# mcu.net
KiCad netlist of a schematic drawn in Altium Designer
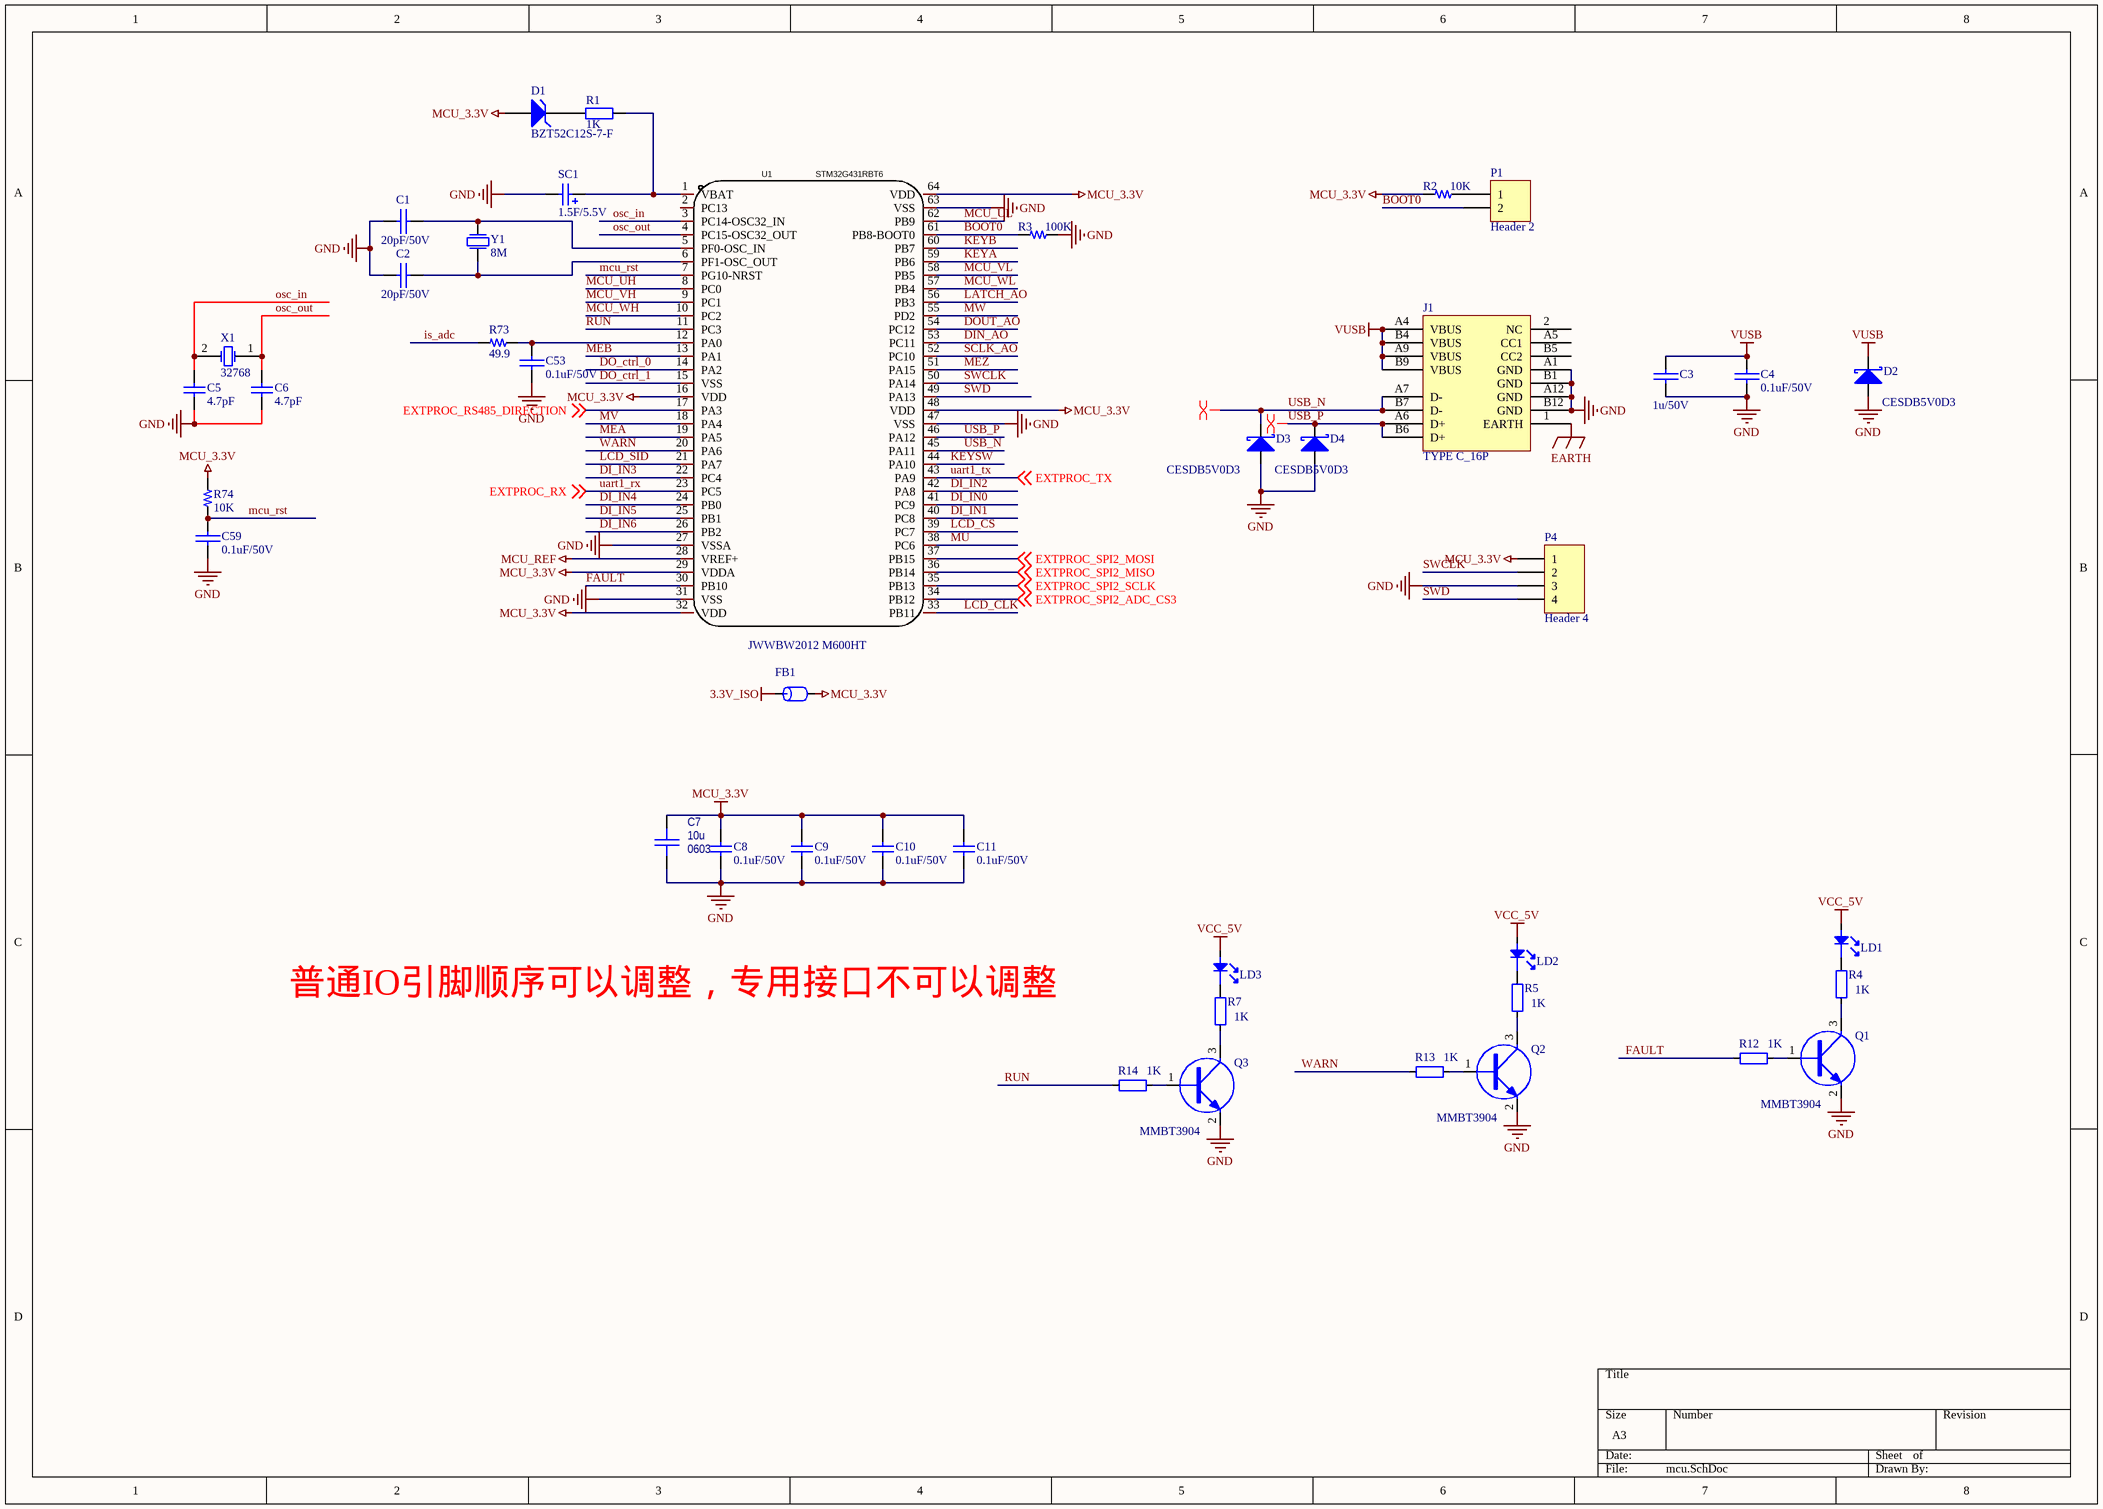
[diagram p0: mcu.SchDoc]

(export (version "E")
  (design (tool "Eeschema 10.0.6"))
  (components
    (comp (ref "C1")
      (value "20pF/50V")
      (footprint "0603C")
      (fields (field (name "Comment") "20pF/25V"))
      (libsource (lib "SM") (part "CAP"))
    )
    (comp (ref "C2")
      (value "20pF/50V")
      (footprint "0603C")
      (fields (field (name "Comment") "20pF/25V"))
      (libsource (lib "SM") (part "CAP"))
    )
    (comp (ref "C3")
      (value "1u/50V")
      (footprint "0603C")
      (fields (field (name "Comment") "1uF/25V"))
      (libsource (lib "SM") (part "CAP"))
    )
    (comp (ref "C4") (value "0.1uF/50V") (footprint "0603C") (libsource (lib "SM") (part "CAP")))
    (comp (ref "C5")
      (value "4.7pF")
      (footprint "0603C")
      (description "Capacitor")
      (fields (field (name "PUBLISHER") "Altium Limited"))
      (libsource (lib "Miscellaneous Devices") (part "Cap"))
    )
    (comp (ref "C6")
      (value "4.7pF")
      (footprint "0603C")
      (description "Capacitor")
      (fields (field (name "PUBLISHER") "Altium Limited"))
      (libsource (lib "Miscellaneous Devices") (part "Cap"))
    )
    (comp (ref "C7")
      (value "10u")
      (footprint "CAPC1608X092N_0603")
      (description "Capacitor, MLCC")
      (fields
        (field (name "MANUFACTURER") "Murata Electronics")
        (field (name "PARTNUMBER") "GRM188R61A106KE69D")
        (field (name "PACKAGE") "0603")
      )
      (libsource (lib "Karl") (part "Capacitor_0603"))
    )
    (comp (ref "C8")
      (value "0.1uF/50V")
      (footprint "0603C")
      (description "Capacitor")
      (fields (field (name "PUBLISHER") "Altium Limited"))
      (libsource (lib "Miscellaneous Devices") (part "Cap"))
    )
    (comp (ref "C9")
      (value "0.1uF/50V")
      (footprint "0603C")
      (description "Capacitor")
      (fields (field (name "PUBLISHER") "Altium Limited"))
      (libsource (lib "Miscellaneous Devices") (part "Cap"))
    )
    (comp (ref "C10")
      (value "0.1uF/50V")
      (footprint "0603C")
      (description "Capacitor")
      (fields (field (name "PUBLISHER") "Altium Limited"))
      (libsource (lib "Miscellaneous Devices") (part "Cap"))
    )
    (comp (ref "C11")
      (value "0.1uF/50V")
      (footprint "0603C")
      (description "Capacitor")
      (fields (field (name "PUBLISHER") "Altium Limited"))
      (libsource (lib "Miscellaneous Devices") (part "Cap"))
    )
    (comp (ref "C53") (value "0.1uF/50V") (footprint "0603C") (libsource (lib "SM") (part "CAP")))
    (comp (ref "C59") (value "0.1uF/50V") (footprint "0603C") (libsource (lib "SM") (part "CAP")))
    (comp (ref "D1")
      (value "BZT52C12S-7-F")
      (footprint "DIOD-SOD323-2_V")
      (libsource (lib "Bogen") (part "BZT52C12S-7-F"))
    )
    (comp (ref "D2") (value "CESDB5V0D3") (footprint "SOD323") (libsource (lib "*") (part "DIODE S")))
    (comp (ref "D3") (value "CESDB5V0D3") (footprint "SOD323") (libsource (lib "*") (part "DIODE S")))
    (comp (ref "D4") (value "CESDB5V0D3") (footprint "SOD323") (libsource (lib "*") (part "DIODE S")))
    (comp (ref "FB1")
      (value "JWWBW2012 M600HT")
      (footprint "0805R")
      (libsource (lib "Schlib_20110825") (part "FB"))
    )
    (comp (ref "J1")
      (value "TYPE C_16P")
      (footprint "TYPEC_16P")
      (libsource (lib "Schlib_20110825") (part "TYPE C_16P"))
    )
    (comp (ref "LD1")
      (value "LED_Green_19-217")
      (footprint "0603led")
      (libsource (lib "RC_M_D_00") (part "LED_Green_19-217"))
    )
    (comp (ref "LD2")
      (value "LED_Green_19-217")
      (footprint "0603led")
      (libsource (lib "RC_M_D_00") (part "LED_Green_19-217"))
    )
    (comp (ref "LD3")
      (value "LED_Green_19-217")
      (footprint "0603led")
      (libsource (lib "RC_M_D_00") (part "LED_Green_19-217"))
    )
    (comp (ref "P1")
      (value "Header 2")
      (footprint "HDR1X2")
      (fields (field (name "PUBLISHER") "Altium Limited"))
      (libsource (lib "Miscellaneous Connectors") (part "Header 2"))
    )
    (comp (ref "P4")
      (value "Header 4")
      (footprint "HDR1X4")
      (fields (field (name "PUBLISHER") "Altium Limited"))
      (libsource (lib "Miscellaneous Connectors") (part "Header 4"))
    )
    (comp (ref "Q1")
      (value "MMBT3904")
      (footprint "SOT23-3")
      (libsource (lib "CenLib") (part "NPN_MMBT3904"))
    )
    (comp (ref "Q2")
      (value "MMBT3904")
      (footprint "SOT23-3")
      (libsource (lib "CenLib") (part "NPN_MMBT3904"))
    )
    (comp (ref "Q3")
      (value "MMBT3904")
      (footprint "SOT23-3")
      (libsource (lib "CenLib") (part "NPN_MMBT3904"))
    )
    (comp (ref "R1") (value "1K") (footprint "0603R") (libsource (lib "MQlibrary") (part "Res0805M")))
    (comp (ref "R2") (value "10K") (footprint "0603R") (libsource (lib "JRJ_1") (part "R")))
    (comp (ref "R3") (value "100K") (footprint "0603R") (libsource (lib "JRJ_1") (part "R")))
    (comp (ref "R4") (value "1K") (footprint "0603r") (libsource (lib "RC_M_D_00") (part "RES0603")))
    (comp (ref "R5") (value "1K") (footprint "0603r") (libsource (lib "RC_M_D_00") (part "RES0603")))
    (comp (ref "R7") (value "1K") (footprint "0603r") (libsource (lib "RC_M_D_00") (part "RES0603")))
    (comp (ref "R12") (value "1K") (footprint "0603r") (libsource (lib "RC_M_D_00") (part "RES0603")))
    (comp (ref "R13") (value "1K") (footprint "0603r") (libsource (lib "RC_M_D_00") (part "RES0603")))
    (comp (ref "R14") (value "1K") (footprint "0603r") (libsource (lib "RC_M_D_00") (part "RES0603")))
    (comp (ref "R73") (value "49.9") (footprint "0603R") (libsource (lib "JRJ_1") (part "R")))
    (comp (ref "R74") (value "10K") (footprint "0603R") (libsource (lib "JRJ_1") (part "R")))
    (comp (ref "SC1")
      (value "1.5F/5.5V")
      (footprint "CAP-TH_DMS3R3224")
      (description "Polarized Capacitor (Axial)")
      (fields (field (name "PUBLISHER") "Altium Limited"))
      (libsource (lib "Miscellaneous Devices") (part "Cap Pol2"))
    )
    (comp (ref "U1")
      (value "STM32G431RBT6")
      (footprint "LQFP-64")
      (fields (field (name "MANUFACTURER") "ST(意法半导体)"))
      (libsource (lib "altium-import") (part "root_0_STM32G431RBT6_"))
    )
    (comp (ref "X1")
      (value "32768")
      (footprint "A")
      (description "Crystal Oscillator")
      (fields (field (name "PUBLISHER") "Altium Limited"))
      (libsource (lib "") (part "XTAL_1"))
    )
    (comp (ref "Y1")
      (value "8M")
      (footprint "CRAY_5032")
      (libsource (lib "Miscellaneous Devices") (part "XTAL"))
    )
  )
  (nets
    (net (code "1") (name "/BOOT0") (class "Default")
      (node (ref "P1") (pin "2") (pinfunction "2_2") (pintype "passive"))
      (node (ref "R3") (pin "1") (pintype "passive"))
      (node (ref "U1") (pin "61") (pinfunction "PB8-BOOT0_61") (pintype "passive"))
    )
    (net (code "2") (name "/DIN_AO") (class "Default")
      (node (ref "U1") (pin "53") (pinfunction "PC11_53") (pintype "passive"))
    )
    (net (code "3") (name "/DI_IN0") (class "Default")
      (node (ref "U1") (pin "41") (pinfunction "PC9_41") (pintype "passive"))
    )
    (net (code "4") (name "/DI_IN1") (class "Default")
      (node (ref "U1") (pin "40") (pinfunction "PC8_40") (pintype "passive"))
    )
    (net (code "5") (name "/DI_IN2") (class "Default")
      (node (ref "U1") (pin "42") (pinfunction "PA8_42") (pintype "passive"))
    )
    (net (code "6") (name "/DI_IN3") (class "Default")
      (node (ref "U1") (pin "22") (pinfunction "PC4_22") (pintype "passive"))
    )
    (net (code "7") (name "/DI_IN4") (class "Default")
      (node (ref "U1") (pin "24") (pinfunction "PB0_24") (pintype "passive"))
    )
    (net (code "8") (name "/DI_IN5") (class "Default")
      (node (ref "U1") (pin "25") (pinfunction "PB1_25") (pintype "passive"))
    )
    (net (code "9") (name "/DI_IN6") (class "Default")
      (node (ref "U1") (pin "26") (pinfunction "PB2_26") (pintype "passive"))
    )
    (net (code "10") (name "/DOUT_AO") (class "Default")
      (node (ref "U1") (pin "54") (pinfunction "PC12_54") (pintype "passive"))
    )
    (net (code "11") (name "/DO_ctrl_0") (class "Default")
      (node (ref "U1") (pin "14") (pinfunction "PA2_14") (pintype "passive"))
    )
    (net (code "12") (name "/DO_ctrl_1") (class "Default")
      (node (ref "U1") (pin "15") (pinfunction "VSS_15") (pintype "passive"))
    )
    (net (code "13") (name "/FAULT") (class "Default")
      (node (ref "R12") (pin "1") (pinfunction "1_1") (pintype "passive"))
      (node (ref "U1") (pin "30") (pinfunction "PB10_30") (pintype "passive"))
    )
    (net (code "14") (name "/KEYA") (class "Default")
      (node (ref "U1") (pin "59") (pinfunction "PB6_59") (pintype "passive"))
    )
    (net (code "15") (name "/KEYB") (class "Default")
      (node (ref "U1") (pin "60") (pinfunction "PB7_60") (pintype "passive"))
    )
    (net (code "16") (name "/KEYSW") (class "Default")
      (node (ref "U1") (pin "44") (pinfunction "PA10_44") (pintype "passive"))
    )
    (net (code "17") (name "/LATCH_AO") (class "Default")
      (node (ref "U1") (pin "56") (pinfunction "PB3_56") (pintype "passive"))
    )
    (net (code "18") (name "/LCD_CLK") (class "Default")
      (node (ref "U1") (pin "33") (pinfunction "PB11_33") (pintype "passive"))
    )
    (net (code "19") (name "/LCD_CS") (class "Default")
      (node (ref "U1") (pin "39") (pinfunction "PC7_39") (pintype "passive"))
    )
    (net (code "20") (name "/LCD_SID") (class "Default")
      (node (ref "U1") (pin "21") (pinfunction "PA7_21") (pintype "passive"))
    )
    (net (code "21") (name "/MCU_UH") (class "Default")
      (node (ref "U1") (pin "8") (pinfunction "PC0_8") (pintype "passive"))
    )
    (net (code "22") (name "/MCU_UL") (class "Default")
      (node (ref "U1") (pin "62") (pinfunction "PB9_62") (pintype "passive"))
    )
    (net (code "23") (name "/MCU_VH") (class "Default")
      (node (ref "U1") (pin "9") (pinfunction "PC1_9") (pintype "passive"))
    )
    (net (code "24") (name "/MCU_VL") (class "Default")
      (node (ref "U1") (pin "58") (pinfunction "PB5_58") (pintype "passive"))
    )
    (net (code "25") (name "/MCU_WH") (class "Default")
      (node (ref "U1") (pin "10") (pinfunction "PC2_10") (pintype "passive"))
    )
    (net (code "26") (name "/MCU_WL") (class "Default")
      (node (ref "U1") (pin "57") (pinfunction "PB4_57") (pintype "passive"))
    )
    (net (code "27") (name "/MEA") (class "Default")
      (node (ref "U1") (pin "19") (pinfunction "PA5_19") (pintype "passive"))
    )
    (net (code "28") (name "/MEB") (class "Default")
      (node (ref "U1") (pin "13") (pinfunction "PA1_13") (pintype "passive"))
    )
    (net (code "29") (name "/MEZ") (class "Default")
      (node (ref "U1") (pin "51") (pinfunction "PA15_51") (pintype "passive"))
    )
    (net (code "30") (name "/MU") (class "Default")
      (node (ref "U1") (pin "38") (pinfunction "PC6_38") (pintype "passive"))
    )
    (net (code "31") (name "/MV") (class "Default")
      (node (ref "U1") (pin "18") (pinfunction "PA4_18") (pintype "passive"))
    )
    (net (code "32") (name "/MW") (class "Default")
      (node (ref "U1") (pin "55") (pinfunction "PD2_55") (pintype "passive"))
    )
    (net (code "33") (name "/RUN") (class "Default")
      (node (ref "R14") (pin "1") (pinfunction "1_1") (pintype "passive"))
      (node (ref "U1") (pin "11") (pinfunction "PC3_11") (pintype "passive"))
    )
    (net (code "34") (name "/SCLK_AO") (class "Default")
      (node (ref "U1") (pin "52") (pinfunction "PC10_52") (pintype "passive"))
    )
    (net (code "35") (name "/SWCLK") (class "Default")
      (node (ref "P4") (pin "2") (pinfunction "2_2") (pintype "passive"))
      (node (ref "U1") (pin "50") (pinfunction "PA14_50") (pintype "passive"))
    )
    (net (code "36") (name "/SWD") (class "Default")
      (node (ref "P4") (pin "4") (pinfunction "4_4") (pintype "passive"))
      (node (ref "U1") (pin "49") (pinfunction "PA13_49") (pintype "passive"))
    )
    (net (code "37") (name "/USB_N") (class "Default")
      (node (ref "D3") (pin "2") (pinfunction "K_2") (pintype "passive"))
      (node (ref "J1") (pin "A7") (pinfunction "D-_A7") (pintype "passive"))
      (node (ref "J1") (pin "B7") (pinfunction "D-_B7") (pintype "passive"))
      (node (ref "U1") (pin "45") (pinfunction "PA11_45") (pintype "passive"))
    )
    (net (code "38") (name "/USB_P") (class "Default")
      (node (ref "D4") (pin "2") (pinfunction "K_2") (pintype "passive"))
      (node (ref "J1") (pin "A6") (pinfunction "D+_A6") (pintype "passive"))
      (node (ref "J1") (pin "B6") (pinfunction "D+_B6") (pintype "passive"))
      (node (ref "U1") (pin "46") (pinfunction "PA12_46") (pintype "passive"))
    )
    (net (code "39") (name "/WARN") (class "Default")
      (node (ref "R13") (pin "1") (pinfunction "1_1") (pintype "passive"))
      (node (ref "U1") (pin "20") (pinfunction "PA6_20") (pintype "passive"))
    )
    (net (code "40") (name "/is_adc") (class "Default") (node (ref "R73") (pin "1") (pintype "passive")))
    (net (code "41") (name "/mcu_rst") (class "Default")
      (node (ref "C59") (pin "2") (pinfunction "2_2") (pintype "passive"))
      (node (ref "R74") (pin "2") (pintype "passive"))
      (node (ref "U1") (pin "7") (pinfunction "PG10-NRST_7") (pintype "passive"))
    )
    (net (code "42") (name "/osc_in") (class "Default")
      (node (ref "C5") (pin "1") (pinfunction "1_1") (pintype "passive"))
      (node (ref "U1") (pin "3") (pinfunction "PC14-OSC32_IN_3") (pintype "passive"))
      (node (ref "X1") (pin "2") (pinfunction "OSC2_2") (pintype "passive"))
    )
    (net (code "43") (name "/osc_out") (class "Default")
      (node (ref "C6") (pin "1") (pinfunction "1_1") (pintype "passive"))
      (node (ref "U1") (pin "4") (pinfunction "PC15-OSC32_OUT_4") (pintype "passive"))
      (node (ref "X1") (pin "1") (pinfunction "OSC1_1") (pintype "passive"))
    )
    (net (code "44") (name "3.3V_ISO") (class "Default") (node (ref "FB1") (pin "1") (pintype "passive")))
    (net (code "45") (name "EARTH") (class "Default")
      (node (ref "J1") (pin "1") (pinfunction "EARTH_1") (pintype "passive"))
    )
    (net (code "46") (name "EXTPROC_RS485_DIRECTION") (class "Default")
      (node (ref "U1") (pin "17") (pinfunction "PA3_17") (pintype "passive"))
    )
    (net (code "47") (name "EXTPROC_RX") (class "Default")
      (node (ref "U1") (pin "23") (pinfunction "PC5_23") (pintype "passive"))
    )
    (net (code "48") (name "EXTPROC_SPI2_ADC_CS3") (class "Default")
      (node (ref "U1") (pin "34") (pinfunction "PB12_34") (pintype "passive"))
    )
    (net (code "49") (name "EXTPROC_SPI2_MISO") (class "Default")
      (node (ref "U1") (pin "36") (pinfunction "PB14_36") (pintype "passive"))
    )
    (net (code "50") (name "EXTPROC_SPI2_MOSI") (class "Default")
      (node (ref "U1") (pin "37") (pinfunction "PB15_37") (pintype "passive"))
    )
    (net (code "51") (name "EXTPROC_SPI2_SCLK") (class "Default")
      (node (ref "U1") (pin "35") (pinfunction "PB13_35") (pintype "passive"))
    )
    (net (code "52") (name "EXTPROC_TX") (class "Default")
      (node (ref "U1") (pin "43") (pinfunction "PA9_43") (pintype "passive"))
    )
    (net (code "53") (name "GND") (class "Default")
      (node (ref "C1") (pin "2") (pinfunction "2_2") (pintype "passive"))
      (node (ref "C10") (pin "1") (pinfunction "1_1") (pintype "passive"))
      (node (ref "C11") (pin "1") (pinfunction "1_1") (pintype "passive"))
      (node (ref "C2") (pin "2") (pinfunction "2_2") (pintype "passive"))
      (node (ref "C3") (pin "1") (pinfunction "1_1") (pintype "passive"))
      (node (ref "C4") (pin "1") (pinfunction "1_1") (pintype "passive"))
      (node (ref "C5") (pin "2") (pinfunction "2_2") (pintype "passive"))
      (node (ref "C53") (pin "1") (pinfunction "1_1") (pintype "passive"))
      (node (ref "C59") (pin "1") (pinfunction "1_1") (pintype "passive"))
      (node (ref "C6") (pin "2") (pinfunction "2_2") (pintype "passive"))
      (node (ref "C7") (pin "2") (pinfunction "2_2") (pintype "passive"))
      (node (ref "C8") (pin "1") (pinfunction "1_1") (pintype "passive"))
      (node (ref "C9") (pin "1") (pinfunction "1_1") (pintype "passive"))
      (node (ref "D2") (pin "1") (pinfunction "A_1") (pintype "passive"))
      (node (ref "D3") (pin "1") (pinfunction "A_1") (pintype "passive"))
      (node (ref "D4") (pin "1") (pinfunction "A_1") (pintype "passive"))
      (node (ref "J1") (pin "A1") (pinfunction "GND_A1") (pintype "passive"))
      (node (ref "J1") (pin "A12") (pinfunction "GND_A12") (pintype "passive"))
      (node (ref "J1") (pin "B1") (pinfunction "GND_B1") (pintype "passive"))
      (node (ref "J1") (pin "B12") (pinfunction "GND_B12") (pintype "passive"))
      (node (ref "P4") (pin "3") (pinfunction "3_3") (pintype "passive"))
      (node (ref "Q1") (pin "2") (pinfunction "E_2") (pintype "passive"))
      (node (ref "Q2") (pin "2") (pinfunction "E_2") (pintype "passive"))
      (node (ref "Q3") (pin "2") (pinfunction "E_2") (pintype "passive"))
      (node (ref "R3") (pin "2") (pintype "passive"))
      (node (ref "SC1") (pin "2") (pinfunction "2_2") (pintype "passive"))
      (node (ref "U1") (pin "27") (pinfunction "VSSA_27") (pintype "passive"))
      (node (ref "U1") (pin "31") (pinfunction "VSS_31") (pintype "passive"))
      (node (ref "U1") (pin "47") (pinfunction "VSS_47") (pintype "passive"))
      (node (ref "U1") (pin "63") (pinfunction "VSS_63") (pintype "passive"))
    )
    (net (code "54") (name "MCU_3.3V") (class "Default")
      (node (ref "C10") (pin "2") (pinfunction "2_2") (pintype "passive"))
      (node (ref "C11") (pin "2") (pinfunction "2_2") (pintype "passive"))
      (node (ref "C7") (pin "1") (pinfunction "1_1") (pintype "passive"))
      (node (ref "C8") (pin "2") (pinfunction "2_2") (pintype "passive"))
      (node (ref "C9") (pin "2") (pinfunction "2_2") (pintype "passive"))
      (node (ref "D1") (pin "1") (pinfunction "A_1") (pintype "passive"))
      (node (ref "FB1") (pin "2") (pintype "passive"))
      (node (ref "P4") (pin "1") (pinfunction "1_1") (pintype "passive"))
      (node (ref "R2") (pin "1") (pintype "passive"))
      (node (ref "R74") (pin "1") (pintype "passive"))
      (node (ref "U1") (pin "16") (pinfunction "VDD_16") (pintype "passive"))
      (node (ref "U1") (pin "29") (pinfunction "VDDA_29") (pintype "passive"))
      (node (ref "U1") (pin "32") (pinfunction "VDD_32") (pintype "passive"))
      (node (ref "U1") (pin "48") (pinfunction "VDD_48") (pintype "passive"))
      (node (ref "U1") (pin "64") (pinfunction "VDD_64") (pintype "passive"))
    )
    (net (code "55") (name "MCU_REF") (class "Default")
      (node (ref "U1") (pin "28") (pinfunction "VREF+_28") (pintype "passive"))
    )
    (net (code "56") (name "Net-(D1-K)") (class "Default")
      (node (ref "D1") (pin "2") (pinfunction "K_2") (pintype "passive"))
      (node (ref "R1") (pin "1") (pinfunction "1_1") (pintype "passive"))
    )
    (net (code "57") (name "Net-(LD1-Pad2)") (class "Default")
      (node (ref "LD1") (pin "2") (pinfunction "2_2") (pintype "passive"))
      (node (ref "R4") (pin "1") (pinfunction "1_1") (pintype "passive"))
    )
    (net (code "58") (name "Net-(LD2-Pad2)") (class "Default")
      (node (ref "LD2") (pin "2") (pinfunction "2_2") (pintype "passive"))
      (node (ref "R5") (pin "1") (pinfunction "1_1") (pintype "passive"))
    )
    (net (code "59") (name "Net-(LD3-Pad2)") (class "Default")
      (node (ref "LD3") (pin "2") (pinfunction "2_2") (pintype "passive"))
      (node (ref "R7") (pin "1") (pinfunction "1_1") (pintype "passive"))
    )
    (net (code "60") (name "Net-(P1-Pad1)") (class "Default")
      (node (ref "P1") (pin "1") (pinfunction "1_1") (pintype "passive"))
      (node (ref "R2") (pin "2") (pintype "passive"))
    )
    (net (code "61") (name "Net-(Q1-B)") (class "Default")
      (node (ref "Q1") (pin "1") (pinfunction "B_1") (pintype "passive"))
      (node (ref "R12") (pin "2") (pinfunction "2_2") (pintype "passive"))
    )
    (net (code "62") (name "Net-(Q1-C)") (class "Default")
      (node (ref "Q1") (pin "3") (pinfunction "C_3") (pintype "passive"))
      (node (ref "R4") (pin "2") (pinfunction "2_2") (pintype "passive"))
    )
    (net (code "63") (name "Net-(Q2-B)") (class "Default")
      (node (ref "Q2") (pin "1") (pinfunction "B_1") (pintype "passive"))
      (node (ref "R13") (pin "2") (pinfunction "2_2") (pintype "passive"))
    )
    (net (code "64") (name "Net-(Q2-C)") (class "Default")
      (node (ref "Q2") (pin "3") (pinfunction "C_3") (pintype "passive"))
      (node (ref "R5") (pin "2") (pinfunction "2_2") (pintype "passive"))
    )
    (net (code "65") (name "Net-(Q3-B)") (class "Default")
      (node (ref "Q3") (pin "1") (pinfunction "B_1") (pintype "passive"))
      (node (ref "R14") (pin "2") (pinfunction "2_2") (pintype "passive"))
    )
    (net (code "66") (name "Net-(Q3-C)") (class "Default")
      (node (ref "Q3") (pin "3") (pinfunction "C_3") (pintype "passive"))
      (node (ref "R7") (pin "2") (pinfunction "2_2") (pintype "passive"))
    )
    (net (code "67") (name "Net-(U1-PA0)") (class "Default")
      (node (ref "C53") (pin "2") (pinfunction "2_2") (pintype "passive"))
      (node (ref "R73") (pin "2") (pintype "passive"))
      (node (ref "U1") (pin "12") (pinfunction "PA0_12") (pintype "passive"))
    )
    (net (code "68") (name "Net-(U1-PF0-OSC_IN)") (class "Default")
      (node (ref "C1") (pin "1") (pinfunction "1_1") (pintype "passive"))
      (node (ref "U1") (pin "5") (pinfunction "PF0-OSC_IN_5") (pintype "passive"))
      (node (ref "Y1") (pin "1") (pinfunction "P1_1") (pintype "passive"))
    )
    (net (code "69") (name "Net-(U1-PF1-OSC_OUT)") (class "Default")
      (node (ref "C2") (pin "1") (pinfunction "1_1") (pintype "passive"))
      (node (ref "U1") (pin "6") (pinfunction "PF1-OSC_OUT_6") (pintype "passive"))
      (node (ref "Y1") (pin "2") (pinfunction "P2_2") (pintype "passive"))
    )
    (net (code "70") (name "Net-(U1-VBAT)") (class "Default")
      (node (ref "R1") (pin "2") (pinfunction "2_2") (pintype "passive"))
      (node (ref "SC1") (pin "1") (pinfunction "1_1") (pintype "passive"))
      (node (ref "U1") (pin "1") (pinfunction "VBAT_1") (pintype "passive"))
    )
    (net (code "71") (name "VCC_5V") (class "Default")
      (node (ref "LD1") (pin "1") (pinfunction "1_1") (pintype "passive"))
      (node (ref "LD2") (pin "1") (pinfunction "1_1") (pintype "passive"))
      (node (ref "LD3") (pin "1") (pinfunction "1_1") (pintype "passive"))
    )
    (net (code "72") (name "VUSB") (class "Default")
      (node (ref "C3") (pin "2") (pinfunction "2_2") (pintype "passive"))
      (node (ref "C4") (pin "2") (pinfunction "2_2") (pintype "passive"))
      (node (ref "D2") (pin "2") (pinfunction "K_2") (pintype "passive"))
      (node (ref "J1") (pin "A4") (pinfunction "VBUS_A4") (pintype "passive"))
      (node (ref "J1") (pin "A9") (pinfunction "VBUS_A9") (pintype "passive"))
      (node (ref "J1") (pin "B4") (pinfunction "VBUS_B4") (pintype "passive"))
      (node (ref "J1") (pin "B9") (pinfunction "VBUS_B9") (pintype "passive"))
    )
    (net (code "73") (name "unconnected-(J1-CC1-PadA5)") (class "Default")
      (node (ref "J1") (pin "A5") (pinfunction "CC1_A5") (pintype "passive"))
    )
    (net (code "74") (name "unconnected-(J1-CC2-PadB5)") (class "Default")
      (node (ref "J1") (pin "B5") (pinfunction "CC2_B5") (pintype "passive"))
    )
    (net (code "75") (name "unconnected-(J1-NC-Pad2)") (class "Default")
      (node (ref "J1") (pin "2") (pinfunction "NC_2") (pintype "passive"))
    )
    (net (code "76") (name "unconnected-(U1-PC13-Pad2)") (class "Default")
      (node (ref "U1") (pin "2") (pinfunction "PC13_2") (pintype "passive"))
    )
  )
)
